# LVDS.net
KiCad netlist of a schematic drawn in EAGLE
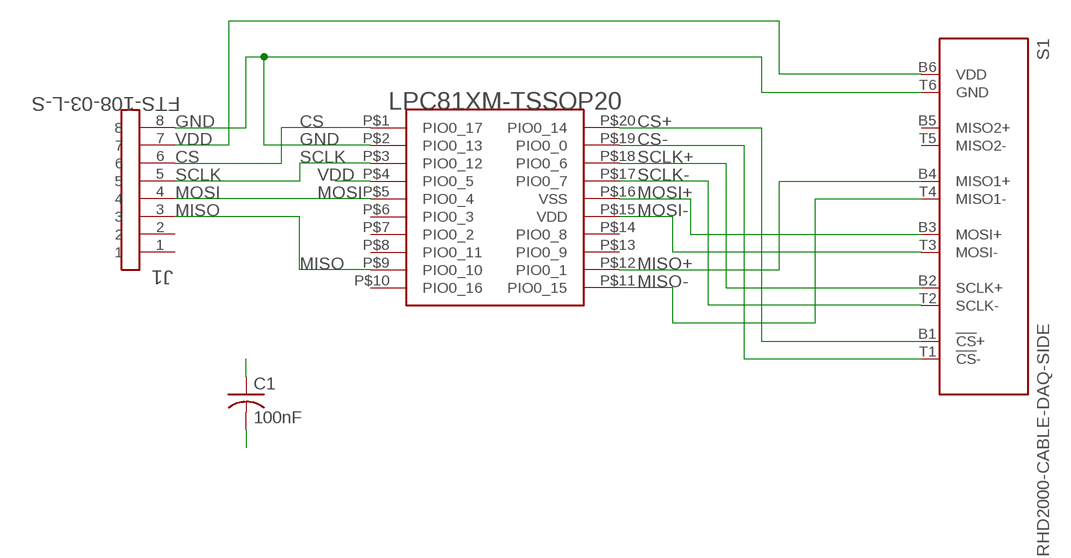
[diagram p0: schematic, sheet 1]

(export (version "E")
  (design (tool "Eeschema 10.0.6"))
  (components
    (comp (ref "C1")
      (value "100nF")
      (footprint "eagle-import:C0402")
      (libsource (lib "eagle-import") (part "C-USC0402"))
    )
    (comp (ref "J1")
      (value "FTS-108-03-L-S")
      (footprint "eagle-import:SAMTEC_FTS-108-03-S")
      (fields (field (name "MPN") "FTS-108-03-L-D"))
      (libsource (lib "eagle-import") (part "FTS-108-03-L-S"))
    )
    (comp (ref "LVDS")
      (value "LPC81XM_TSSOP20")
      (footprint "eagle-import:TSSOP20")
      (libsource (lib "eagle-import") (part "LPC81XM_TSSOP20"))
    )
    (comp (ref "S1")
      (value "RHD2000-CABLE-DAQ-SIDE")
      (footprint "eagle-import:OMNETICS_PZN-12-AA")
      (libsource (lib "eagle-import") (part "RHD2000-CABLE-DAQ-SIDE"))
    )
  )
  (nets
    (net (code "1") (name "/CS") (class "Default")
      (node (ref "J1") (pin "6") (pinfunction "6_6") (pintype "passive"))
      (node (ref "LVDS") (pin "P$1") (pinfunction "PIO0_17_P$1") (pintype "bidirectional"))
    )
    (net (code "2") (name "/CS+") (class "Default")
      (node (ref "LVDS") (pin "P$20") (pinfunction "PIO0_14_P$20") (pintype "bidirectional"))
      (node (ref "S1") (pin "B1") (pinfunction "~{CS}+_B1") (pintype "bidirectional"))
    )
    (net (code "3") (name "/CS-") (class "Default")
      (node (ref "LVDS") (pin "P$19") (pinfunction "PIO0_0_P$19") (pintype "bidirectional"))
      (node (ref "S1") (pin "T1") (pinfunction "~{CS}-_T1") (pintype "bidirectional"))
    )
    (net (code "4") (name "/GND") (class "Default")
      (node (ref "C1") (pin "2") (pinfunction "2_2") (pintype "passive"))
      (node (ref "J1") (pin "8") (pinfunction "8_8") (pintype "passive"))
      (node (ref "LVDS") (pin "P$2") (pinfunction "PIO0_13_P$2") (pintype "bidirectional"))
      (node (ref "S1") (pin "T6") (pinfunction "GND_T6") (pintype "power_in"))
    )
    (net (code "5") (name "/MISO") (class "Default")
      (node (ref "J1") (pin "3") (pinfunction "3_3") (pintype "passive"))
      (node (ref "LVDS") (pin "P$9") (pinfunction "PIO0_10_P$9") (pintype "bidirectional"))
    )
    (net (code "6") (name "/MISO+") (class "Default")
      (node (ref "LVDS") (pin "P$12") (pinfunction "PIO0_1_P$12") (pintype "bidirectional"))
      (node (ref "S1") (pin "B4") (pinfunction "MISO1+_B4") (pintype "bidirectional"))
    )
    (net (code "7") (name "/MISO-") (class "Default")
      (node (ref "LVDS") (pin "P$11") (pinfunction "PIO0_15_P$11") (pintype "bidirectional"))
      (node (ref "S1") (pin "T4") (pinfunction "MISO1-_T4") (pintype "bidirectional"))
    )
    (net (code "8") (name "/MOSI") (class "Default")
      (node (ref "J1") (pin "4") (pinfunction "4_4") (pintype "passive"))
      (node (ref "LVDS") (pin "P$5") (pinfunction "PIO0_4_P$5") (pintype "bidirectional"))
    )
    (net (code "9") (name "/MOSI+") (class "Default")
      (node (ref "LVDS") (pin "P$16") (pinfunction "VSS_P$16") (pintype "bidirectional"))
      (node (ref "S1") (pin "B3") (pinfunction "MOSI+_B3") (pintype "bidirectional"))
    )
    (net (code "10") (name "/MOSI-") (class "Default")
      (node (ref "LVDS") (pin "P$15") (pinfunction "VDD_P$15") (pintype "bidirectional"))
      (node (ref "S1") (pin "T3") (pinfunction "MOSI-_T3") (pintype "bidirectional"))
    )
    (net (code "11") (name "/SCLK") (class "Default")
      (node (ref "J1") (pin "5") (pinfunction "5_5") (pintype "passive"))
      (node (ref "LVDS") (pin "P$3") (pinfunction "PIO0_12_P$3") (pintype "bidirectional"))
    )
    (net (code "12") (name "/SCLK+") (class "Default")
      (node (ref "LVDS") (pin "P$18") (pinfunction "PIO0_6_P$18") (pintype "bidirectional"))
      (node (ref "S1") (pin "B2") (pinfunction "SCLK+_B2") (pintype "bidirectional"))
    )
    (net (code "13") (name "/SCLK-") (class "Default")
      (node (ref "LVDS") (pin "P$17") (pinfunction "PIO0_7_P$17") (pintype "bidirectional"))
      (node (ref "S1") (pin "T2") (pinfunction "SCLK-_T2") (pintype "bidirectional"))
    )
    (net (code "14") (name "/VDD") (class "Default")
      (node (ref "C1") (pin "1") (pinfunction "1_1") (pintype "passive"))
      (node (ref "J1") (pin "7") (pinfunction "7_7") (pintype "passive"))
      (node (ref "LVDS") (pin "P$4") (pinfunction "PIO0_5_P$4") (pintype "bidirectional"))
      (node (ref "S1") (pin "B6") (pinfunction "VDD_B6") (pintype "bidirectional"))
    )
    (net (code "15") (name "unconnected-(J1-Pad1)") (class "Default")
      (node (ref "J1") (pin "1") (pinfunction "1_1") (pintype "passive"))
    )
    (net (code "16") (name "unconnected-(J1-Pad2)") (class "Default")
      (node (ref "J1") (pin "2") (pinfunction "2_2") (pintype "passive"))
    )
    (net (code "17") (name "unconnected-(LVDS-PIO0_2-PadP$7)") (class "Default")
      (node (ref "LVDS") (pin "P$7") (pinfunction "PIO0_2_P$7") (pintype "bidirectional"))
    )
    (net (code "18") (name "unconnected-(LVDS-PIO0_3-PadP$6)") (class "Default")
      (node (ref "LVDS") (pin "P$6") (pinfunction "PIO0_3_P$6") (pintype "bidirectional"))
    )
    (net (code "19") (name "unconnected-(LVDS-PIO0_8-PadP$14)") (class "Default")
      (node (ref "LVDS") (pin "P$14") (pinfunction "PIO0_8_P$14") (pintype "bidirectional"))
    )
    (net (code "20") (name "unconnected-(LVDS-PIO0_9-PadP$13)") (class "Default")
      (node (ref "LVDS") (pin "P$13") (pinfunction "PIO0_9_P$13") (pintype "bidirectional"))
    )
    (net (code "21") (name "unconnected-(LVDS-PIO0_11-PadP$8)") (class "Default")
      (node (ref "LVDS") (pin "P$8") (pinfunction "PIO0_11_P$8") (pintype "bidirectional"))
    )
    (net (code "22") (name "unconnected-(LVDS-PIO0_16-PadP$10)") (class "Default")
      (node (ref "LVDS") (pin "P$10") (pinfunction "PIO0_16_P$10") (pintype "bidirectional"))
    )
    (net (code "23") (name "unconnected-(S1-MISO2+-PadB5)") (class "Default")
      (node (ref "S1") (pin "B5") (pinfunction "MISO2+_B5") (pintype "bidirectional"))
    )
    (net (code "24") (name "unconnected-(S1-MISO2--PadT5)") (class "Default")
      (node (ref "S1") (pin "T5") (pinfunction "MISO2-_T5") (pintype "bidirectional"))
    )
  )
)
